# Stepper_Motor2.net
KiCad netlist of a schematic drawn in Altium Designer
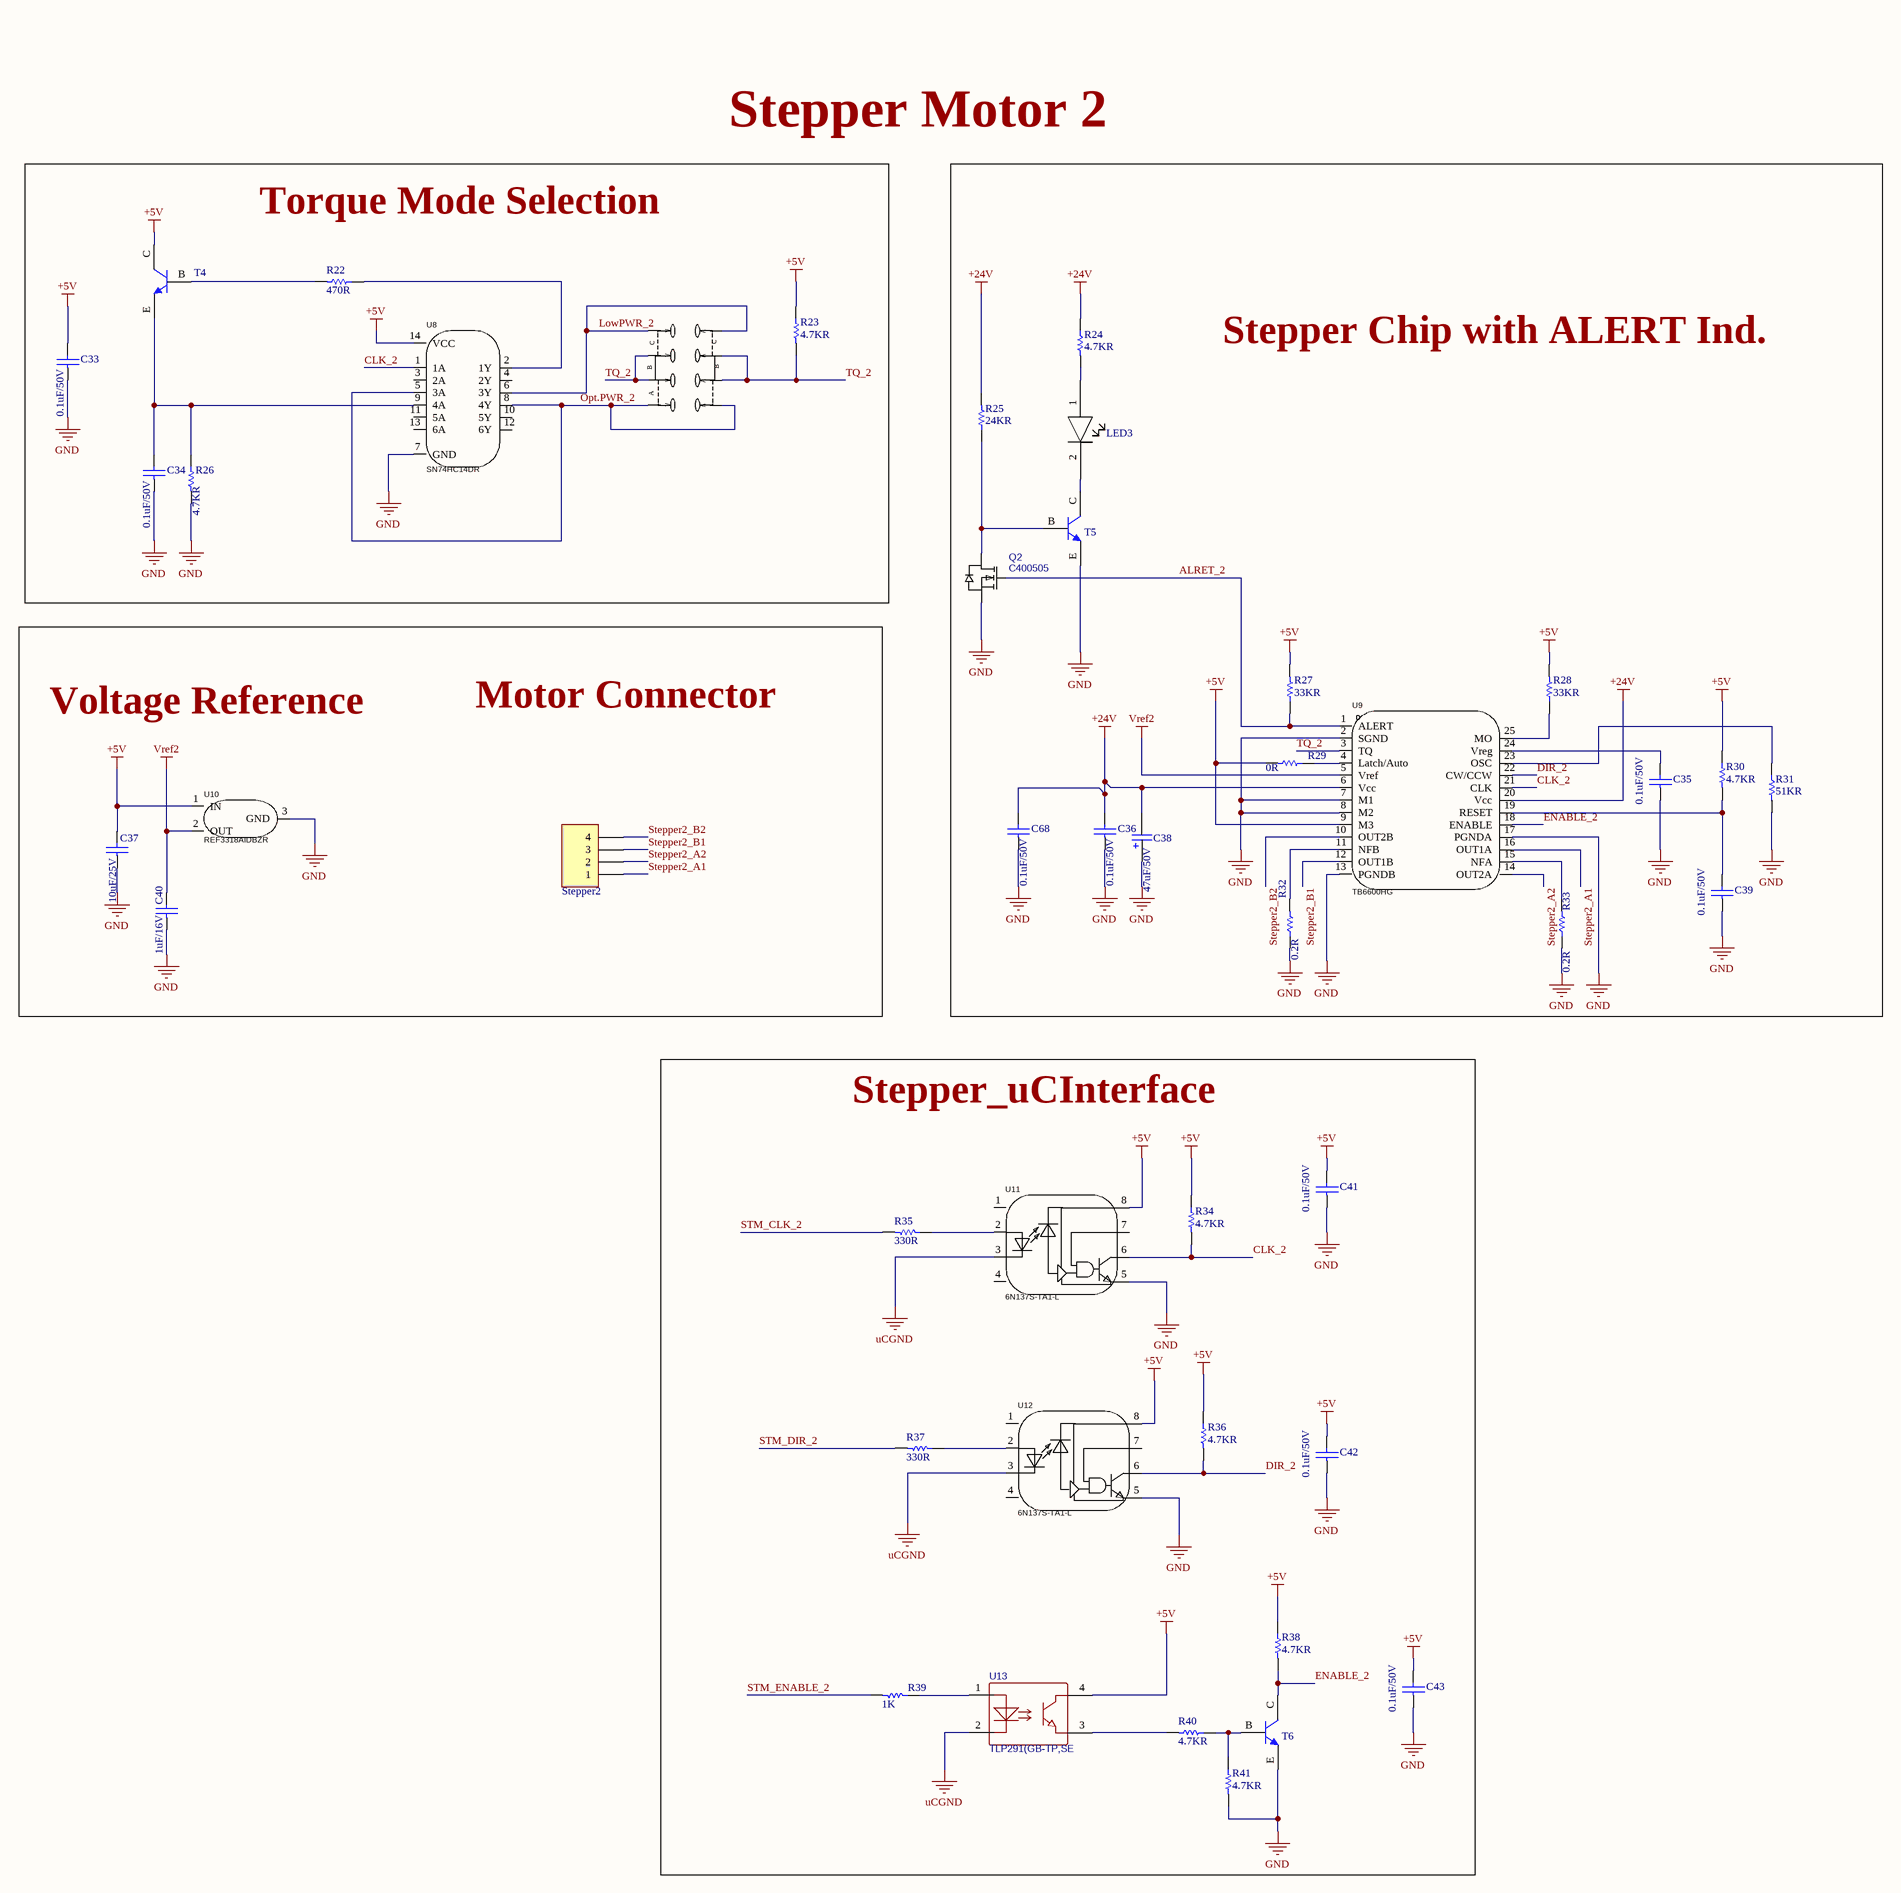
[diagram p0: Stepper Motor2.SchDoc]

(export (version "E")
  (design (tool "Eeschema 10.0.6"))
  (components
    (comp (ref "C33")
      (value "0.1uF/50V")
      (footprint "PCBComponent_1")
      (description "C1591")
      (fields (field (name "CREATED BY") "NourAldin"))
      (libsource (lib "0603 Capacitor") (part "0603 Capacitor"))
    )
    (comp (ref "C34")
      (value "0.1uF/50V")
      (footprint "PCBComponent_1")
      (description "C1591")
      (fields (field (name "CREATED BY") "NourAldin"))
      (libsource (lib "0603 Capacitor") (part "0603 Capacitor"))
    )
    (comp (ref "C35")
      (value "0.1uF/50V")
      (footprint "PCBComponent_1")
      (description "C1591")
      (fields (field (name "CREATED BY") "NourAldin"))
      (libsource (lib "0603 Capacitor") (part "0603 Capacitor"))
    )
    (comp (ref "C36")
      (value "0.1uF/50V")
      (footprint "PCBComponent_1")
      (description "C1591")
      (fields (field (name "CREATED BY") "NourAldin"))
      (libsource (lib "0603 Capacitor") (part "0603 Capacitor"))
    )
    (comp (ref "C37")
      (value "10uF/25V")
      (footprint "PCBComponent_1")
      (description "C96446")
      (fields (field (name "CREATED BY") "NourAldin"))
      (libsource (lib "0603 Capacitor") (part "0603 Capacitor"))
    )
    (comp (ref "C38")
      (value "47uF/50V")
      (footprint "CAPLEAD_D6.3mm")
      (description "C45100")
      (fields
        (field (name "MANUFACTURER") "KEMET")
        (field (name "MANUFACTURER PART NUMBER") "A759EQ475M2AAAE160")
      )
      (libsource (lib "GlobalLib") (part "A759EQ475M2AAAE160"))
    )
    (comp (ref "C39")
      (value "0.1uF/50V")
      (footprint "PCBComponent_1")
      (description "C1591")
      (fields (field (name "CREATED BY") "NourAldin"))
      (libsource (lib "0603 Capacitor") (part "0603 Capacitor"))
    )
    (comp (ref "C40")
      (value "1uF/16V")
      (footprint "PCBComponent_1")
      (description "C1592")
      (fields (field (name "CREATED BY") "NourAldin"))
      (libsource (lib "0603 Capacitor") (part "0603 Capacitor"))
    )
    (comp (ref "C41")
      (value "0.1uF/50V")
      (footprint "PCBComponent_1")
      (description "C1591")
      (fields (field (name "CREATED BY") "NourAldin"))
      (libsource (lib "0603 Capacitor") (part "0603 Capacitor"))
    )
    (comp (ref "C42")
      (value "0.1uF/50V")
      (footprint "PCBComponent_1")
      (description "C1591")
      (fields (field (name "CREATED BY") "NourAldin"))
      (libsource (lib "0603 Capacitor") (part "0603 Capacitor"))
    )
    (comp (ref "C43")
      (value "0.1uF/50V")
      (footprint "PCBComponent_1")
      (description "C1591")
      (fields (field (name "CREATED BY") "NourAldin"))
      (libsource (lib "0603 Capacitor") (part "0603 Capacitor"))
    )
    (comp (ref "C68")
      (value "0.1uF/50V")
      (footprint "PCBComponent_1")
      (description "C1591")
      (fields (field (name "CREATED BY") "NourAldin"))
      (libsource (lib "0603 Capacitor") (part "0603 Capacitor"))
    )
    (comp (ref "LED3")
      (value "1206 LED")
      (footprint "1206 LED")
      (description "C434438")
      (fields (field (name "CREATED BY") "NourAldin"))
      (libsource (lib "1206 LED") (part "1206 LED"))
    )
    (comp (ref "Q2")
      (value "C400505")
      (footprint "SOT-23-3_L2.9-W1.3-P1.90-LS2.4-BR")
      (fields
        (field (name "MANUFACTURER") "YANGJIE(扬杰)")
        (field (name "MANUFACTURER PART") "BSS138")
        (field (name "CONTRIBUTOR") "LCSC")
      )
      (libsource (lib "DIVERSE") (part "BSS138_MOSFET"))
    )
    (comp (ref "R22")
      (value "470R")
      (footprint "RESC1608X06N")
      (description "C114669")
      (fields (field (name "CREATED BY") "NourAldin"))
      (libsource (lib "0603 Resistor") (part "0603 Resistor"))
    )
    (comp (ref "R23")
      (value "4.7KR")
      (footprint "R0402")
      (description "C105871")
      (libsource (lib "DIVERSE") (part "0402 Resistor"))
    )
    (comp (ref "R24")
      (value "4.7KR")
      (footprint "R0402")
      (description "C105871")
      (libsource (lib "DIVERSE") (part "0402 Resistor"))
    )
    (comp (ref "R25")
      (value "24KR")
      (footprint "RESC1608X06N")
      (description "C2930081")
      (fields (field (name "CREATED BY") "NourAldin"))
      (libsource (lib "0603 Resistor") (part "0603 Resistor"))
    )
    (comp (ref "R26")
      (value "4.7KR")
      (footprint "R0402")
      (description "C105871")
      (libsource (lib "DIVERSE") (part "0402 Resistor"))
    )
    (comp (ref "R27")
      (value "33KR")
      (footprint "RESC1608X06N")
      (description "C126359")
      (fields (field (name "CREATED BY") "NourAldin"))
      (libsource (lib "0603 Resistor") (part "0603 Resistor"))
    )
    (comp (ref "R28")
      (value "33KR")
      (footprint "RESC1608X06N")
      (description "C126359")
      (fields (field (name "CREATED BY") "NourAldin"))
      (libsource (lib "0603 Resistor") (part "0603 Resistor"))
    )
    (comp (ref "R29")
      (value "0R")
      (footprint "RESC1608X06N")
      (description "C100044")
      (fields (field (name "CREATED BY") "NourAldin"))
      (libsource (lib "0603 Resistor") (part "0603 Resistor"))
    )
    (comp (ref "R30")
      (value "4.7KR")
      (footprint "R0402")
      (description "C105871")
      (libsource (lib "DIVERSE") (part "0402 Resistor"))
    )
    (comp (ref "R31")
      (value "51KR")
      (footprint "R0402")
      (description "C107230")
      (libsource (lib "DIVERSE") (part "0402 Resistor"))
    )
    (comp (ref "R32")
      (value "0.2R")
      (footprint "RESC6431X12N")
      (description "C2903473")
      (fields (field (name "CREATED BY") "NourAldin"))
      (libsource (lib "2512 Resistor") (part "2512 Resistor"))
    )
    (comp (ref "R33")
      (value "0.2R")
      (footprint "RESC6431X12N")
      (description "C2903473")
      (fields (field (name "CREATED BY") "NourAldin"))
      (libsource (lib "2512 Resistor") (part "2512 Resistor"))
    )
    (comp (ref "R34")
      (value "4.7KR")
      (footprint "R0402")
      (description "C105871")
      (libsource (lib "DIVERSE") (part "0402 Resistor"))
    )
    (comp (ref "R35")
      (value "330R")
      (footprint "R0402")
      (description "C105875")
      (libsource (lib "DIVERSE") (part "0402 Resistor"))
    )
    (comp (ref "R36")
      (value "4.7KR")
      (footprint "R0402")
      (description "C105871")
      (libsource (lib "DIVERSE") (part "0402 Resistor"))
    )
    (comp (ref "R37")
      (value "330R")
      (footprint "R0402")
      (description "C105875")
      (libsource (lib "DIVERSE") (part "0402 Resistor"))
    )
    (comp (ref "R38")
      (value "4.7KR")
      (footprint "R0402")
      (description "C105871")
      (libsource (lib "DIVERSE") (part "0402 Resistor"))
    )
    (comp (ref "R39")
      (value "1K")
      (footprint "R0402")
      (description "C106235")
      (libsource (lib "DIVERSE") (part "0402 Resistor"))
    )
    (comp (ref "R40")
      (value "4.7KR")
      (footprint "R0402")
      (description "C105871")
      (libsource (lib "DIVERSE") (part "0402 Resistor"))
    )
    (comp (ref "R41")
      (value "4.7KR")
      (footprint "R0402")
      (description "C105871")
      (libsource (lib "DIVERSE") (part "0402 Resistor"))
    )
    (comp (ref "Stepper2")
      (value "Header 4 Pin Polar")
      (footprint "PCBComponent_1")
      (libsource (lib "Header 4 Pin Polar") (part "Header 4 Pin Polar"))
    )
    (comp (ref "SW2")
      (value "MST23D19G2")
      (footprint "SW-SMD_MST23D19G2")
      (description "C431545")
      (fields (field (name "MANUFACTURER") "SHOU HAN(首韩)"))
      (libsource (lib "LIB") (part "MST23D19G2"))
    )
    (comp (ref "T4")
      (value "MMBT3904 Transistor")
      (footprint "MMBT3904")
      (description "C108429")
      (fields (field (name "CREATED BY") "NourAldin"))
      (libsource (lib "MMBT3904 Transistor") (part "MMBT3904 Transistor"))
    )
    (comp (ref "T5")
      (value "MMBT3904 Transistor")
      (footprint "MMBT3904")
      (description "C108429")
      (fields (field (name "CREATED BY") "NourAldin"))
      (libsource (lib "MMBT3904 Transistor") (part "MMBT3904 Transistor"))
    )
    (comp (ref "T6")
      (value "MMBT3904 Transistor")
      (footprint "MMBT3904")
      (description "C108429")
      (fields (field (name "CREATED BY") "NourAldin"))
      (libsource (lib "MMBT3904 Transistor") (part "MMBT3904 Transistor"))
    )
    (comp (ref "U8")
      (value "SN74HC14DR")
      (footprint "SOIC-14_L8.7-W3.9-P1.27-LS6.0-BL")
      (description "C6820")
      (fields (field (name "MANUFACTURER") "TI(德州仪器)"))
      (libsource (lib "LIB") (part "SN74HC14DR"))
    )
    (comp (ref "U9")
      (value "TB6600HG")
      (footprint "HZIP25-P-1.00F")
      (description "C66042")
      (fields (field (name "MANUFACTURER") "TOSHIBA(东芝)"))
      (libsource (lib "LIB") (part "TB6600HG"))
    )
    (comp (ref "U10")
      (value "REF3318AIDBZR")
      (footprint "SOT-23-3_L2.9-W1.3-P1.90-LS2.4-BR")
      (description "C115877")
      (fields (field (name "MANUFACTURER") "TI(德州仪器)") (field (name "TOLERANCE") "±0.15%"))
      (libsource (lib "LIB") (part "REF3318AIDBZR"))
    )
    (comp (ref "U11")
      (value "6N137S-TA1-L")
      (footprint "SOP-8_L9.8-W6.6-P2.54-LS10.3-BL")
      (description "C92651")
      (fields (field (name "MANUFACTURER") "LITEON(光宝)"))
      (libsource (lib "LIB") (part "6N137S-TA1-L"))
    )
    (comp (ref "U12")
      (value "6N137S-TA1-L")
      (footprint "SOP-8_L9.8-W6.6-P2.54-LS10.3-BL")
      (description "C92651")
      (fields (field (name "MANUFACTURER") "LITEON(光宝)"))
      (libsource (lib "LIB") (part "6N137S-TA1-L"))
    )
    (comp (ref "U13")
      (value "TLP291(GB-TP,SE")
      (footprint "SOP-4-1.27mm")
      (description "C55144")
      (libsource (lib "CO2_Lib") (part "TLP291(GB-TP,SE(T"))
    )
  )
  (nets
    (net (code "1") (name "+5V") (class "Default")
      (node (ref "C33") (pin "2") (pinfunction "2_2") (pintype "passive"))
      (node (ref "C37") (pin "2") (pinfunction "2_2") (pintype "passive"))
      (node (ref "C41") (pin "2") (pinfunction "2_2") (pintype "passive"))
      (node (ref "C42") (pin "2") (pinfunction "2_2") (pintype "passive"))
      (node (ref "C43") (pin "2") (pinfunction "2_2") (pintype "passive"))
      (node (ref "R23") (pin "1") (pinfunction "1_1") (pintype "passive"))
      (node (ref "R27") (pin "2") (pinfunction "2_2") (pintype "passive"))
      (node (ref "R28") (pin "2") (pinfunction "2_2") (pintype "passive"))
      (node (ref "R29") (pin "2") (pinfunction "2_2") (pintype "passive"))
      (node (ref "R30") (pin "1") (pinfunction "1_1") (pintype "passive"))
      (node (ref "R34") (pin "1") (pinfunction "1_1") (pintype "passive"))
      (node (ref "R36") (pin "1") (pinfunction "1_1") (pintype "passive"))
      (node (ref "R38") (pin "1") (pinfunction "1_1") (pintype "passive"))
      (node (ref "T4") (pin "C") (pinfunction "C_C") (pintype "passive"))
      (node (ref "U10") (pin "1") (pinfunction "IN_1") (pintype "passive"))
      (node (ref "U11") (pin "8") (pinfunction "8_8") (pintype "passive"))
      (node (ref "U12") (pin "8") (pinfunction "8_8") (pintype "passive"))
      (node (ref "U13") (pin "4") (pinfunction "4_4") (pintype "passive"))
      (node (ref "U8") (pin "14") (pinfunction "VCC_14") (pintype "passive"))
      (node (ref "U9") (pin "9") (pinfunction "M3_9") (pintype "passive"))
    )
    (net (code "2") (name "+24V") (class "Default")
      (node (ref "C36") (pin "2") (pinfunction "2_2") (pintype "passive"))
      (node (ref "C38") (pin "2") (pinfunction "2_2") (pintype "passive"))
      (node (ref "C68") (pin "2") (pinfunction "2_2") (pintype "passive"))
      (node (ref "R24") (pin "1") (pinfunction "1_1") (pintype "passive"))
      (node (ref "R25") (pin "2") (pinfunction "2_2") (pintype "passive"))
      (node (ref "U9") (pin "20") (pinfunction "Vcc_20") (pintype "passive"))
      (node (ref "U9") (pin "6") (pinfunction "Vcc_6") (pintype "passive"))
    )
    (net (code "3") (name "/ALRET_2") (class "Default")
      (node (ref "Q2") (pin "1") (pinfunction "G_1") (pintype "passive"))
      (node (ref "R27") (pin "1") (pinfunction "1_1") (pintype "passive"))
      (node (ref "U9") (pin "1") (pinfunction "ALERT_1") (pintype "passive"))
    )
    (net (code "4") (name "/CLK_2") (class "Default")
      (node (ref "R34") (pin "2") (pinfunction "2_2") (pintype "passive"))
      (node (ref "U11") (pin "6") (pinfunction "6_6") (pintype "passive"))
      (node (ref "U8") (pin "1") (pinfunction "1A_1") (pintype "passive"))
      (node (ref "U9") (pin "21") (pinfunction "CLK_21") (pintype "passive"))
    )
    (net (code "5") (name "/DIR_2") (class "Default")
      (node (ref "R36") (pin "2") (pinfunction "2_2") (pintype "passive"))
      (node (ref "U12") (pin "6") (pinfunction "6_6") (pintype "passive"))
      (node (ref "U9") (pin "22") (pinfunction "CW/CCW_22") (pintype "passive"))
    )
    (net (code "6") (name "/ENABLE_2") (class "Default")
      (node (ref "R38") (pin "2") (pinfunction "2_2") (pintype "passive"))
      (node (ref "T6") (pin "C") (pinfunction "C_C") (pintype "passive"))
      (node (ref "U9") (pin "18") (pinfunction "ENABLE_18") (pintype "passive"))
    )
    (net (code "7") (name "/LowPWR_2") (class "Default")
      (node (ref "SW2") (pin "4") (pinfunction "4_4") (pintype "passive"))
      (node (ref "SW2") (pin "5") (pinfunction "5_5") (pintype "passive"))
      (node (ref "U8") (pin "6") (pinfunction "3Y_6") (pintype "passive"))
    )
    (net (code "8") (name "/Opt.PWR_2") (class "Default")
      (node (ref "SW2") (pin "1") (pinfunction "1_1") (pintype "passive"))
      (node (ref "SW2") (pin "8") (pinfunction "8_8") (pintype "passive"))
      (node (ref "U8") (pin "5") (pinfunction "3A_5") (pintype "passive"))
      (node (ref "U8") (pin "8") (pinfunction "4Y_8") (pintype "passive"))
    )
    (net (code "9") (name "/STM_CLK_2") (class "Default")
      (node (ref "R35") (pin "2") (pinfunction "2_2") (pintype "passive"))
    )
    (net (code "10") (name "/STM_DIR_2") (class "Default")
      (node (ref "R37") (pin "2") (pinfunction "2_2") (pintype "passive"))
    )
    (net (code "11") (name "/STM_ENABLE_2") (class "Default")
      (node (ref "R39") (pin "2") (pinfunction "2_2") (pintype "passive"))
    )
    (net (code "12") (name "/Stepper2_A1") (class "Default")
      (node (ref "Stepper2") (pin "1") (pinfunction "1_1") (pintype "passive"))
      (node (ref "U9") (pin "16") (pinfunction "OUT1A_16") (pintype "passive"))
    )
    (net (code "13") (name "/Stepper2_A2") (class "Default")
      (node (ref "Stepper2") (pin "2") (pinfunction "2_2") (pintype "passive"))
      (node (ref "U9") (pin "14") (pinfunction "OUT2A_14") (pintype "passive"))
    )
    (net (code "14") (name "/Stepper2_B1") (class "Default")
      (node (ref "Stepper2") (pin "3") (pinfunction "3_3") (pintype "passive"))
      (node (ref "U9") (pin "12") (pinfunction "OUT1B_12") (pintype "passive"))
    )
    (net (code "15") (name "/Stepper2_B2") (class "Default")
      (node (ref "Stepper2") (pin "4") (pinfunction "4_4") (pintype "passive"))
      (node (ref "U9") (pin "10") (pinfunction "OUT2B_10") (pintype "passive"))
    )
    (net (code "16") (name "/TQ_2") (class "Default")
      (node (ref "R23") (pin "2") (pinfunction "2_2") (pintype "passive"))
      (node (ref "SW2") (pin "2") (pinfunction "2_2") (pintype "passive"))
      (node (ref "SW2") (pin "3") (pinfunction "3_3") (pintype "passive"))
      (node (ref "SW2") (pin "6") (pinfunction "6_6") (pintype "passive"))
      (node (ref "SW2") (pin "7") (pinfunction "7_7") (pintype "passive"))
      (node (ref "U9") (pin "3") (pinfunction "TQ_3") (pintype "passive"))
    )
    (net (code "17") (name "GND") (class "Default")
      (node (ref "C33") (pin "1") (pinfunction "1_1") (pintype "passive"))
      (node (ref "C34") (pin "1") (pinfunction "1_1") (pintype "passive"))
      (node (ref "C35") (pin "1") (pinfunction "1_1") (pintype "passive"))
      (node (ref "C36") (pin "1") (pinfunction "1_1") (pintype "passive"))
      (node (ref "C37") (pin "1") (pinfunction "1_1") (pintype "passive"))
      (node (ref "C38") (pin "1") (pinfunction "1_1") (pintype "passive"))
      (node (ref "C39") (pin "1") (pinfunction "1_1") (pintype "passive"))
      (node (ref "C40") (pin "1") (pinfunction "1_1") (pintype "passive"))
      (node (ref "C41") (pin "1") (pinfunction "1_1") (pintype "passive"))
      (node (ref "C42") (pin "1") (pinfunction "1_1") (pintype "passive"))
      (node (ref "C43") (pin "1") (pinfunction "1_1") (pintype "passive"))
      (node (ref "C68") (pin "1") (pinfunction "1_1") (pintype "passive"))
      (node (ref "Q2") (pin "2") (pinfunction "S_2") (pintype "passive"))
      (node (ref "R26") (pin "2") (pinfunction "2_2") (pintype "passive"))
      (node (ref "R31") (pin "2") (pinfunction "2_2") (pintype "passive"))
      (node (ref "R32") (pin "1") (pinfunction "1_1") (pintype "passive"))
      (node (ref "R33") (pin "1") (pinfunction "1_1") (pintype "passive"))
      (node (ref "R41") (pin "2") (pinfunction "2_2") (pintype "passive"))
      (node (ref "T5") (pin "E") (pinfunction "E_E") (pintype "passive"))
      (node (ref "T6") (pin "E") (pinfunction "E_E") (pintype "passive"))
      (node (ref "U10") (pin "3") (pinfunction "GND_3") (pintype "passive"))
      (node (ref "U11") (pin "5") (pinfunction "5_5") (pintype "passive"))
      (node (ref "U12") (pin "5") (pinfunction "5_5") (pintype "passive"))
      (node (ref "U8") (pin "7") (pinfunction "GND_7") (pintype "passive"))
      (node (ref "U9") (pin "13") (pinfunction "PGNDB_13") (pintype "passive"))
      (node (ref "U9") (pin "17") (pinfunction "PGNDA_17") (pintype "passive"))
      (node (ref "U9") (pin "2") (pinfunction "SGND_2") (pintype "passive"))
      (node (ref "U9") (pin "7") (pinfunction "M1_7") (pintype "passive"))
      (node (ref "U9") (pin "8") (pinfunction "M2_8") (pintype "passive"))
    )
    (net (code "18") (name "Net-(LED3-Pad1)") (class "Default")
      (node (ref "LED3") (pin "1") (pinfunction "1_1") (pintype "passive"))
      (node (ref "R24") (pin "2") (pinfunction "2_2") (pintype "passive"))
    )
    (net (code "19") (name "Net-(LED3-Pad2)") (class "Default")
      (node (ref "LED3") (pin "2") (pinfunction "2_2") (pintype "passive"))
      (node (ref "T5") (pin "C") (pinfunction "C_C") (pintype "passive"))
    )
    (net (code "20") (name "Net-(Q2-D)") (class "Default")
      (node (ref "Q2") (pin "3") (pinfunction "D_3") (pintype "passive"))
      (node (ref "R25") (pin "1") (pinfunction "1_1") (pintype "passive"))
      (node (ref "T5") (pin "B") (pinfunction "B_B") (pintype "passive"))
    )
    (net (code "21") (name "Net-(R22-Pad2)") (class "Default")
      (node (ref "R22") (pin "2") (pinfunction "2_2") (pintype "passive"))
      (node (ref "T4") (pin "B") (pinfunction "B_B") (pintype "passive"))
    )
    (net (code "22") (name "Net-(R35-Pad1)") (class "Default")
      (node (ref "R35") (pin "1") (pinfunction "1_1") (pintype "passive"))
      (node (ref "U11") (pin "2") (pinfunction "2_2") (pintype "passive"))
    )
    (net (code "23") (name "Net-(R37-Pad1)") (class "Default")
      (node (ref "R37") (pin "1") (pinfunction "1_1") (pintype "passive"))
      (node (ref "U12") (pin "2") (pinfunction "2_2") (pintype "passive"))
    )
    (net (code "24") (name "Net-(R39-Pad1)") (class "Default")
      (node (ref "R39") (pin "1") (pinfunction "1_1") (pintype "passive"))
      (node (ref "U13") (pin "1") (pinfunction "1_1") (pintype "passive"))
    )
    (net (code "25") (name "Net-(R40-Pad1)") (class "Default")
      (node (ref "R40") (pin "1") (pinfunction "1_1") (pintype "passive"))
      (node (ref "R41") (pin "1") (pinfunction "1_1") (pintype "passive"))
      (node (ref "T6") (pin "B") (pinfunction "B_B") (pintype "passive"))
    )
    (net (code "26") (name "Net-(R40-Pad2)") (class "Default")
      (node (ref "R40") (pin "2") (pinfunction "2_2") (pintype "passive"))
      (node (ref "U13") (pin "3") (pinfunction "3_3") (pintype "passive"))
    )
    (net (code "27") (name "Net-(U8-1Y)") (class "Default")
      (node (ref "R22") (pin "1") (pinfunction "1_1") (pintype "passive"))
      (node (ref "U8") (pin "2") (pinfunction "1Y_2") (pintype "passive"))
    )
    (net (code "28") (name "Net-(U8-4A)") (class "Default")
      (node (ref "C34") (pin "2") (pinfunction "2_2") (pintype "passive"))
      (node (ref "R26") (pin "1") (pinfunction "1_1") (pintype "passive"))
      (node (ref "T4") (pin "E") (pinfunction "E_E") (pintype "passive"))
      (node (ref "U8") (pin "9") (pinfunction "4A_9") (pintype "passive"))
    )
    (net (code "29") (name "Net-(U9-Latch{slash}Auto)") (class "Default")
      (node (ref "R29") (pin "1") (pinfunction "1_1") (pintype "passive"))
      (node (ref "U9") (pin "4") (pinfunction "Latch/Auto_4") (pintype "passive"))
    )
    (net (code "30") (name "Net-(U9-MO)") (class "Default")
      (node (ref "R28") (pin "1") (pinfunction "1_1") (pintype "passive"))
      (node (ref "U9") (pin "25") (pinfunction "MO_25") (pintype "passive"))
    )
    (net (code "31") (name "Net-(U9-NFA)") (class "Default")
      (node (ref "R33") (pin "2") (pinfunction "2_2") (pintype "passive"))
      (node (ref "U9") (pin "15") (pinfunction "NFA_15") (pintype "passive"))
    )
    (net (code "32") (name "Net-(U9-NFB)") (class "Default")
      (node (ref "R32") (pin "2") (pinfunction "2_2") (pintype "passive"))
      (node (ref "U9") (pin "11") (pinfunction "NFB_11") (pintype "passive"))
    )
    (net (code "33") (name "Net-(U9-OSC)") (class "Default")
      (node (ref "R31") (pin "1") (pinfunction "1_1") (pintype "passive"))
      (node (ref "U9") (pin "23") (pinfunction "OSC_23") (pintype "passive"))
    )
    (net (code "34") (name "Net-(U9-RESET)") (class "Default")
      (node (ref "C39") (pin "2") (pinfunction "2_2") (pintype "passive"))
      (node (ref "R30") (pin "2") (pinfunction "2_2") (pintype "passive"))
      (node (ref "U9") (pin "19") (pinfunction "RESET_19") (pintype "passive"))
    )
    (net (code "35") (name "Net-(U9-Vreg)") (class "Default")
      (node (ref "C35") (pin "2") (pinfunction "2_2") (pintype "passive"))
      (node (ref "U9") (pin "24") (pinfunction "Vreg_24") (pintype "passive"))
    )
    (net (code "36") (name "Vref2") (class "Default")
      (node (ref "C40") (pin "2") (pinfunction "2_2") (pintype "passive"))
      (node (ref "U10") (pin "2") (pinfunction "OUT_2") (pintype "passive"))
      (node (ref "U9") (pin "5") (pinfunction "Vref_5") (pintype "passive"))
    )
    (net (code "37") (name "uCGND") (class "Default")
      (node (ref "U11") (pin "3") (pinfunction "3_3") (pintype "passive"))
      (node (ref "U12") (pin "3") (pinfunction "3_3") (pintype "passive"))
      (node (ref "U13") (pin "2") (pinfunction "2_2") (pintype "passive"))
    )
    (net (code "38") (name "unconnected-(U8-2A-Pad3)") (class "Default")
      (node (ref "U8") (pin "3") (pinfunction "2A_3") (pintype "passive"))
    )
    (net (code "39") (name "unconnected-(U8-2Y-Pad4)") (class "Default")
      (node (ref "U8") (pin "4") (pinfunction "2Y_4") (pintype "passive"))
    )
    (net (code "40") (name "unconnected-(U8-5A-Pad11)") (class "Default")
      (node (ref "U8") (pin "11") (pinfunction "5A_11") (pintype "passive"))
    )
    (net (code "41") (name "unconnected-(U8-5Y-Pad10)") (class "Default")
      (node (ref "U8") (pin "10") (pinfunction "5Y_10") (pintype "passive"))
    )
    (net (code "42") (name "unconnected-(U8-6A-Pad13)") (class "Default")
      (node (ref "U8") (pin "13") (pinfunction "6A_13") (pintype "passive"))
    )
    (net (code "43") (name "unconnected-(U8-6Y-Pad12)") (class "Default")
      (node (ref "U8") (pin "12") (pinfunction "6Y_12") (pintype "passive"))
    )
    (net (code "44") (name "unconnected-(U11-NC-Pad1)") (class "Default")
      (node (ref "U11") (pin "1") (pinfunction "NC_1") (pintype "passive"))
    )
    (net (code "45") (name "unconnected-(U11-NC-Pad4)") (class "Default")
      (node (ref "U11") (pin "4") (pinfunction "NC_4") (pintype "passive"))
    )
    (net (code "46") (name "unconnected-(U11-Pad7)") (class "Default")
      (node (ref "U11") (pin "7") (pinfunction "7_7") (pintype "passive"))
    )
    (net (code "47") (name "unconnected-(U12-NC-Pad1)") (class "Default")
      (node (ref "U12") (pin "1") (pinfunction "NC_1") (pintype "passive"))
    )
    (net (code "48") (name "unconnected-(U12-NC-Pad4)") (class "Default")
      (node (ref "U12") (pin "4") (pinfunction "NC_4") (pintype "passive"))
    )
    (net (code "49") (name "unconnected-(U12-Pad7)") (class "Default")
      (node (ref "U12") (pin "7") (pinfunction "7_7") (pintype "passive"))
    )
  )
)
